# Osmofl2k_adapter_smaonly.net
KiCad netlist of a schematic drawn in EAGLE
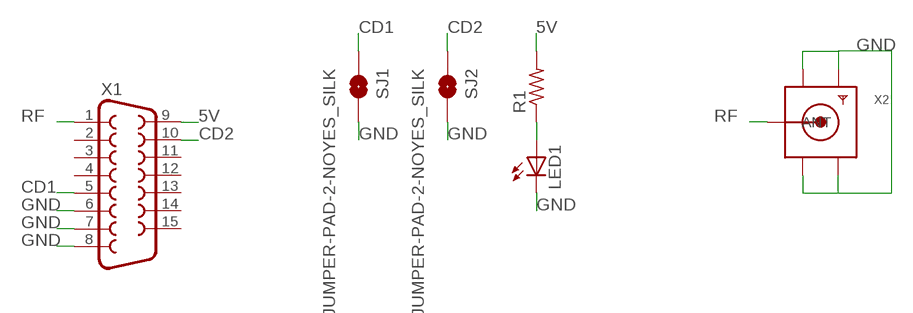
[diagram p0: schematic, sheet 1]

(export (version "E")
  (design (tool "Eeschema 10.0.6"))
  (components
    (comp (ref "LED1")
      (value "LEDCHIPLED_0805")
      (footprint "eagle-import:CHIPLED_0805")
      (libsource (lib "eagle-import") (part "LEDCHIPLED_0805"))
    )
    (comp (ref "R1")
      (value "R-US_R0805")
      (footprint "eagle-import:R0805")
      (libsource (lib "eagle-import") (part "R-US_R0805"))
    )
    (comp (ref "SJ1")
      (value "JUMPER-PAD-2-NOYES_SILK")
      (footprint "eagle-import:PAD-JUMPER-2-NO_YES_SILK")
      (libsource (lib "eagle-import") (part "JUMPER-PAD-2-NOYES_SILK"))
    )
    (comp (ref "SJ2")
      (value "JUMPER-PAD-2-NOYES_SILK")
      (footprint "eagle-import:PAD-JUMPER-2-NO_YES_SILK")
      (libsource (lib "eagle-import") (part "JUMPER-PAD-2-NOYES_SILK"))
    )
    (comp (ref "X1")
      (value "F15HDH")
      (footprint "eagle-import:HDF15H")
      (libsource (lib "eagle-import") (part "F15HDH"))
    )
    (comp (ref "X2")
      (value "SMACONNECTOR_EDGE")
      (footprint "eagle-import:SMA_EDGELAUNCH")
      (libsource (lib "eagle-import") (part "SMACONNECTOR_EDGE"))
    )
  )
  (nets
    (net (code "1") (name "/5V") (class "Default")
      (node (ref "R1") (pin "2") (pinfunction "2_2") (pintype "passive"))
      (node (ref "X1") (pin "9") (pinfunction "9_9") (pintype "passive"))
    )
    (net (code "2") (name "/CD1") (class "Default")
      (node (ref "SJ1") (pin "1") (pinfunction "1_1") (pintype "passive"))
      (node (ref "X1") (pin "5") (pinfunction "5_5") (pintype "passive"))
    )
    (net (code "3") (name "/CD2") (class "Default")
      (node (ref "SJ2") (pin "1") (pinfunction "1_1") (pintype "passive"))
      (node (ref "X1") (pin "10") (pinfunction "10_10") (pintype "passive"))
    )
    (net (code "4") (name "/GND") (class "Default")
      (node (ref "LED1") (pin "C") (pinfunction "C_C") (pintype "passive"))
      (node (ref "SJ1") (pin "2") (pinfunction "2_2") (pintype "passive"))
      (node (ref "SJ2") (pin "2") (pinfunction "2_2") (pintype "passive"))
      (node (ref "X1") (pin "6") (pinfunction "6_6") (pintype "passive"))
      (node (ref "X1") (pin "7") (pinfunction "7_7") (pintype "passive"))
      (node (ref "X1") (pin "8") (pinfunction "8_8") (pintype "passive"))
      (node (ref "X2") (pin "GND@1") (pinfunction "GND4_GND@1") (pintype "power_in"))
      (node (ref "X2") (pin "GND@2") (pinfunction "GND3_GND@2") (pintype "power_in"))
      (node (ref "X2") (pin "GND@3") (pinfunction "GND2_GND@3") (pintype "power_in"))
      (node (ref "X2") (pin "GND@4") (pinfunction "GND1_GND@4") (pintype "power_in"))
    )
    (net (code "5") (name "/RF") (class "Default")
      (node (ref "X1") (pin "1") (pinfunction "1_1") (pintype "passive"))
      (node (ref "X2") (pin "P") (pinfunction "ANT_P") (pintype "bidirectional"))
    )
    (net (code "6") (name "Net-(LED1-PadA)") (class "Default")
      (node (ref "LED1") (pin "A") (pinfunction "A_A") (pintype "passive"))
      (node (ref "R1") (pin "1") (pinfunction "1_1") (pintype "passive"))
    )
    (net (code "7") (name "unconnected-(X1-Pad2)") (class "Default")
      (node (ref "X1") (pin "2") (pinfunction "2_2") (pintype "passive"))
    )
    (net (code "8") (name "unconnected-(X1-Pad3)") (class "Default")
      (node (ref "X1") (pin "3") (pinfunction "3_3") (pintype "passive"))
    )
    (net (code "9") (name "unconnected-(X1-Pad4)") (class "Default")
      (node (ref "X1") (pin "4") (pinfunction "4_4") (pintype "passive"))
    )
    (net (code "10") (name "unconnected-(X1-Pad11)") (class "Default")
      (node (ref "X1") (pin "11") (pinfunction "11_11") (pintype "passive"))
    )
    (net (code "11") (name "unconnected-(X1-Pad12)") (class "Default")
      (node (ref "X1") (pin "12") (pinfunction "12_12") (pintype "passive"))
    )
    (net (code "12") (name "unconnected-(X1-Pad13)") (class "Default")
      (node (ref "X1") (pin "13") (pinfunction "13_13") (pintype "passive"))
    )
    (net (code "13") (name "unconnected-(X1-Pad14)") (class "Default")
      (node (ref "X1") (pin "14") (pinfunction "14_14") (pintype "passive"))
    )
    (net (code "14") (name "unconnected-(X1-Pad15)") (class "Default")
      (node (ref "X1") (pin "15") (pinfunction "15_15") (pintype "passive"))
    )
  )
)
